# PUB3.net
KiCad netlist of a schematic drawn in EasyEDA Pro
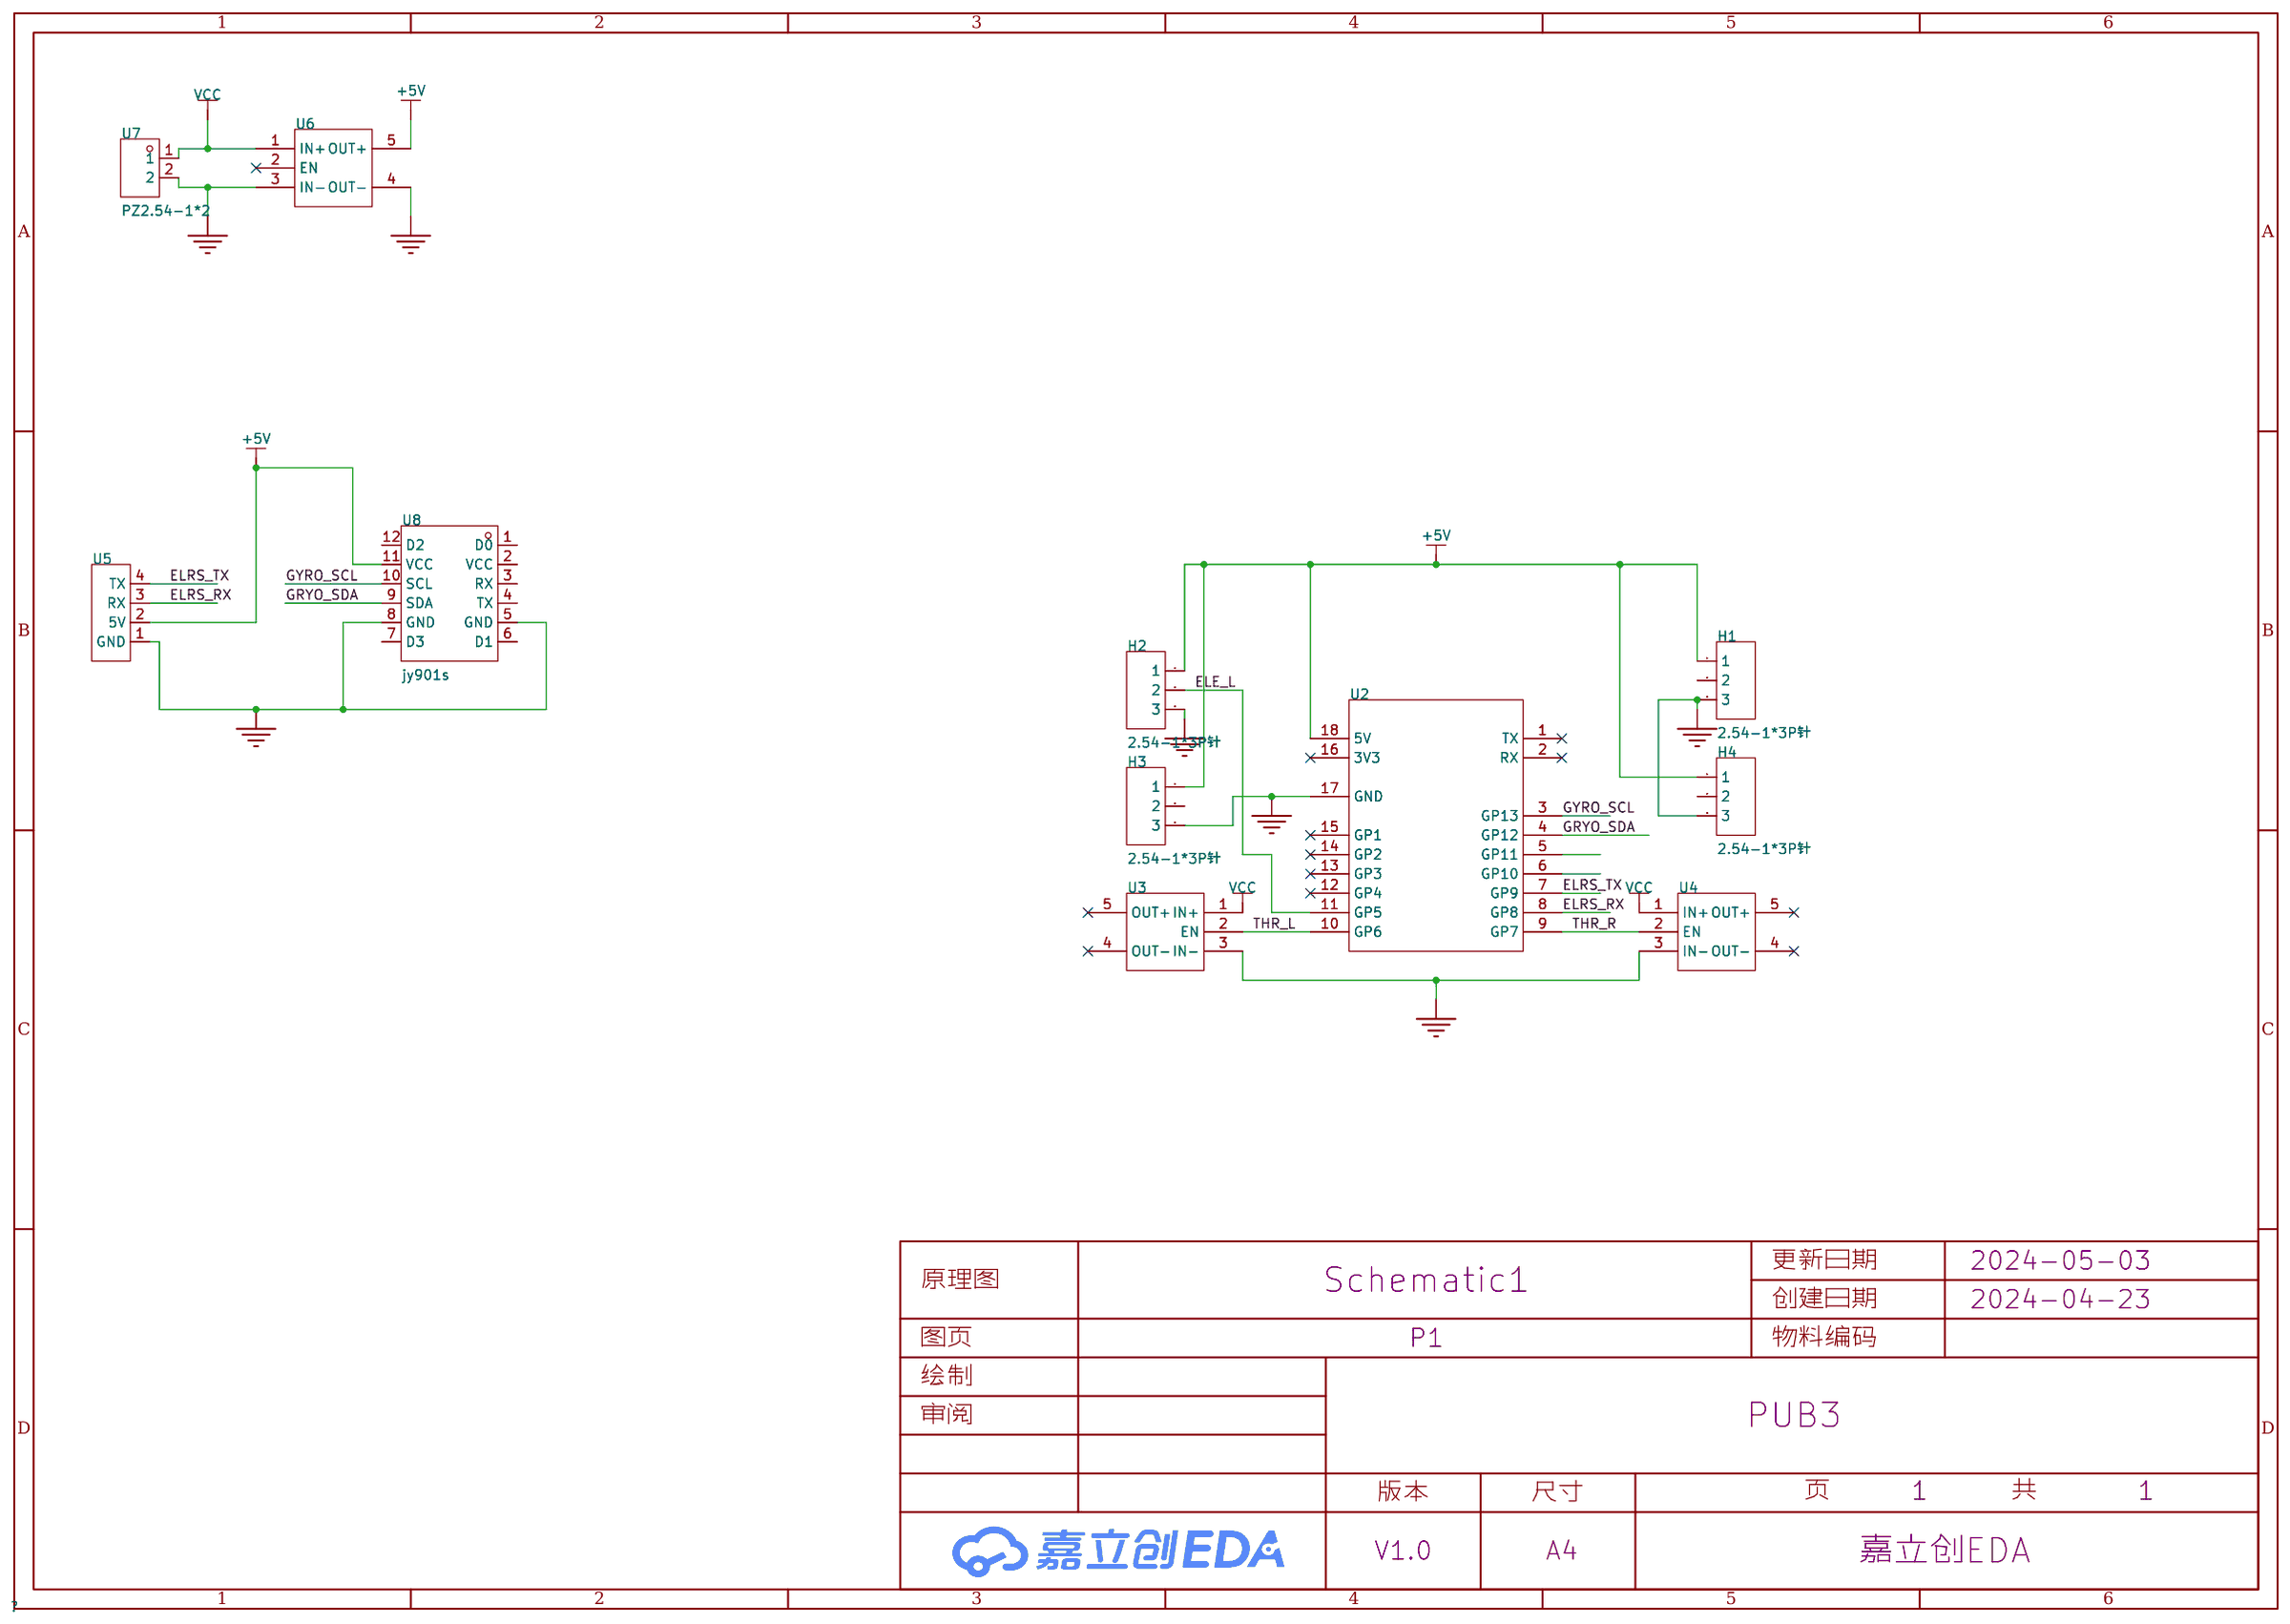
[diagram p0: schematic sheet]

(export (version "E")
  (design (tool "Eeschema 10.0.6"))
  (components
    (comp (ref "H1")
      (value "2.54-1*3P针")
      (footprint "easyedapro:HDR-TH_3P-P2.54-V-M-1")
      (fields (field (name "Manufacturer") "BOOMELE(博穆精密)"))
      (libsource (lib "easyedapro") (part "Header-Male-2.54_1x3"))
    )
    (comp (ref "H2")
      (value "2.54-1*3P针")
      (footprint "easyedapro:HDR-TH_3P-P2.54-V-M-1")
      (fields (field (name "Manufacturer") "BOOMELE(博穆精密)"))
      (libsource (lib "easyedapro") (part "Header-Male-2.54_1x3"))
    )
    (comp (ref "H3")
      (value "2.54-1*3P针")
      (footprint "easyedapro:HDR-TH_3P-P2.54-V-M-1")
      (fields (field (name "Manufacturer") "BOOMELE(博穆精密)"))
      (libsource (lib "easyedapro") (part "Header-Male-2.54_1x3"))
    )
    (comp (ref "H4")
      (value "2.54-1*3P针")
      (footprint "easyedapro:HDR-TH_3P-P2.54-V-M-1")
      (fields (field (name "Manufacturer") "BOOMELE(博穆精密)"))
      (libsource (lib "easyedapro") (part "Header-Male-2.54_1x3"))
    )
    (comp (ref "U2")
      (value "~")
      (footprint "easyedapro:ESP32-S3-Zero")
      (libsource (lib "easyedapro") (part "ESP32-S3-Zero"))
    )
    (comp (ref "U3")
      (value "~")
      (footprint "easyedapro:带有使能端的DC-DC降压模块")
      (libsource (lib "easyedapro") (part "带有使能端的DC-DC降压模块"))
    )
    (comp (ref "U4")
      (value "~")
      (footprint "easyedapro:带有使能端的DC-DC降压模块")
      (libsource (lib "easyedapro") (part "带有使能端的DC-DC降压模块"))
    )
    (comp (ref "U5")
      (value "~")
      (footprint "easyedapro:ELRS焊盘")
      (libsource (lib "easyedapro") (part "ELRS焊盘"))
    )
    (comp (ref "U6")
      (value "~")
      (footprint "easyedapro:带有使能端的DC-DC降压模块")
      (libsource (lib "easyedapro") (part "带有使能端的DC-DC降压模块"))
    )
    (comp (ref "U7")
      (value "PZ2.54-1*2")
      (footprint "easyedapro:HDR-TH_2P-P2.54-V-M-3")
      (fields (field (name "Manufacturer") "ZHOURI(洲日)"))
      (libsource (lib "easyedapro") (part "PZ2.54-1*2"))
    )
    (comp (ref "U8")
      (value "jy901s")
      (footprint "easyedapro:COMM-SMD_JY901S-1")
      (libsource (lib "easyedapro") (part "JY901S"))
    )
  )
  (nets
    (net (code "1") (name "+5V") (class "Default")
      (node (ref "H1") (pin "1") (pinfunction "1_1") (pintype "input"))
      (node (ref "H2") (pin "1") (pinfunction "1_1") (pintype "input"))
      (node (ref "H3") (pin "1") (pinfunction "1_1") (pintype "input"))
      (node (ref "H4") (pin "1") (pinfunction "1_1") (pintype "input"))
      (node (ref "U2") (pin "18") (pinfunction "5V_18") (pintype "input"))
      (node (ref "U5") (pin "2") (pinfunction "5V_2") (pintype "input"))
      (node (ref "U6") (pin "5") (pinfunction "OUT+_5") (pintype "output"))
      (node (ref "U8") (pin "11") (pinfunction "VCC_11") (pintype "unspecified"))
    )
    (net (code "2") (name "/ELE_L") (class "Default")
      (node (ref "H2") (pin "2") (pinfunction "2_2") (pintype "input"))
      (node (ref "U2") (pin "11") (pinfunction "GP5_11") (pintype "input"))
    )
    (net (code "3") (name "/ELRS_RX") (class "Default")
      (node (ref "U2") (pin "8") (pinfunction "GP8_8") (pintype "input"))
      (node (ref "U5") (pin "3") (pinfunction "RX_3") (pintype "input"))
    )
    (net (code "4") (name "/ELRS_TX") (class "Default")
      (node (ref "U2") (pin "7") (pinfunction "GP9_7") (pintype "input"))
      (node (ref "U5") (pin "4") (pinfunction "TX_4") (pintype "input"))
    )
    (net (code "5") (name "/GRYO_SDA") (class "Default")
      (node (ref "U2") (pin "4") (pinfunction "GP12_4") (pintype "input"))
      (node (ref "U8") (pin "9") (pinfunction "SDA_9") (pintype "unspecified"))
    )
    (net (code "6") (name "/GYRO_SCL") (class "Default")
      (node (ref "U2") (pin "3") (pinfunction "GP13_3") (pintype "input"))
      (node (ref "U8") (pin "10") (pinfunction "SCL_10") (pintype "unspecified"))
    )
    (net (code "7") (name "/THR_L") (class "Default")
      (node (ref "U2") (pin "10") (pinfunction "GP6_10") (pintype "input"))
      (node (ref "U3") (pin "2") (pinfunction "EN_2") (pintype "input"))
    )
    (net (code "8") (name "/THR_R") (class "Default")
      (node (ref "U2") (pin "9") (pinfunction "GP7_9") (pintype "input"))
      (node (ref "U4") (pin "2") (pinfunction "EN_2") (pintype "input"))
    )
    (net (code "9") (name "GND") (class "Default")
      (node (ref "H1") (pin "3") (pinfunction "3_3") (pintype "input"))
      (node (ref "H2") (pin "3") (pinfunction "3_3") (pintype "input"))
      (node (ref "H3") (pin "3") (pinfunction "3_3") (pintype "input"))
      (node (ref "H4") (pin "3") (pinfunction "3_3") (pintype "input"))
      (node (ref "U2") (pin "17") (pinfunction "GND_17") (pintype "input"))
      (node (ref "U3") (pin "3") (pinfunction "IN-_3") (pintype "input"))
      (node (ref "U4") (pin "3") (pinfunction "IN-_3") (pintype "input"))
      (node (ref "U5") (pin "1") (pinfunction "GND_1") (pintype "input"))
      (node (ref "U6") (pin "3") (pinfunction "IN-_3") (pintype "input"))
      (node (ref "U6") (pin "4") (pinfunction "OUT-_4") (pintype "output"))
      (node (ref "U7") (pin "2") (pinfunction "2_2") (pintype "unspecified"))
      (node (ref "U8") (pin "5") (pinfunction "GND_5") (pintype "unspecified"))
      (node (ref "U8") (pin "8") (pinfunction "GND_8") (pintype "unspecified"))
    )
    (net (code "10") (name "VCC") (class "Default")
      (node (ref "U3") (pin "1") (pinfunction "IN+_1") (pintype "input"))
      (node (ref "U4") (pin "1") (pinfunction "IN+_1") (pintype "input"))
      (node (ref "U6") (pin "1") (pinfunction "IN+_1") (pintype "input"))
      (node (ref "U7") (pin "1") (pinfunction "1_1") (pintype "unspecified"))
    )
    (net (code "11") (name "unconnected-(H1-Pad2)") (class "Default")
      (node (ref "H1") (pin "2") (pinfunction "2_2") (pintype "input"))
    )
    (net (code "12") (name "unconnected-(H3-Pad2)") (class "Default")
      (node (ref "H3") (pin "2") (pinfunction "2_2") (pintype "input"))
    )
    (net (code "13") (name "unconnected-(H4-Pad2)") (class "Default")
      (node (ref "H4") (pin "2") (pinfunction "2_2") (pintype "input"))
    )
    (net (code "14") (name "unconnected-(U2-3V3-Pad16)") (class "Default")
      (node (ref "U2") (pin "16") (pinfunction "3V3_16") (pintype "input+no_connect"))
    )
    (net (code "15") (name "unconnected-(U2-GP1-Pad15)") (class "Default")
      (node (ref "U2") (pin "15") (pinfunction "GP1_15") (pintype "input+no_connect"))
    )
    (net (code "16") (name "unconnected-(U2-GP2-Pad14)") (class "Default")
      (node (ref "U2") (pin "14") (pinfunction "GP2_14") (pintype "input+no_connect"))
    )
    (net (code "17") (name "unconnected-(U2-GP3-Pad13)") (class "Default")
      (node (ref "U2") (pin "13") (pinfunction "GP3_13") (pintype "input+no_connect"))
    )
    (net (code "18") (name "unconnected-(U2-GP4-Pad12)") (class "Default")
      (node (ref "U2") (pin "12") (pinfunction "GP4_12") (pintype "input+no_connect"))
    )
    (net (code "19") (name "unconnected-(U2-GP10-Pad6)") (class "Default")
      (node (ref "U2") (pin "6") (pinfunction "GP10_6") (pintype "input"))
    )
    (net (code "20") (name "unconnected-(U2-GP11-Pad5)") (class "Default")
      (node (ref "U2") (pin "5") (pinfunction "GP11_5") (pintype "input"))
    )
    (net (code "21") (name "unconnected-(U2-RX-Pad2)") (class "Default")
      (node (ref "U2") (pin "2") (pinfunction "RX_2") (pintype "input+no_connect"))
    )
    (net (code "22") (name "unconnected-(U2-TX-Pad1)") (class "Default")
      (node (ref "U2") (pin "1") (pinfunction "TX_1") (pintype "input+no_connect"))
    )
    (net (code "23") (name "unconnected-(U3-OUT+-Pad5)") (class "Default")
      (node (ref "U3") (pin "5") (pinfunction "OUT+_5") (pintype "output+no_connect"))
    )
    (net (code "24") (name "unconnected-(U3-OUT--Pad4)") (class "Default")
      (node (ref "U3") (pin "4") (pinfunction "OUT-_4") (pintype "output+no_connect"))
    )
    (net (code "25") (name "unconnected-(U4-OUT+-Pad5)") (class "Default")
      (node (ref "U4") (pin "5") (pinfunction "OUT+_5") (pintype "output+no_connect"))
    )
    (net (code "26") (name "unconnected-(U4-OUT--Pad4)") (class "Default")
      (node (ref "U4") (pin "4") (pinfunction "OUT-_4") (pintype "output+no_connect"))
    )
    (net (code "27") (name "unconnected-(U6-EN-Pad2)") (class "Default")
      (node (ref "U6") (pin "2") (pinfunction "EN_2") (pintype "input+no_connect"))
    )
    (net (code "28") (name "unconnected-(U8-D0-Pad1)") (class "Default")
      (node (ref "U8") (pin "1") (pinfunction "D0_1") (pintype "unspecified"))
    )
    (net (code "29") (name "unconnected-(U8-D1-Pad6)") (class "Default")
      (node (ref "U8") (pin "6") (pinfunction "D1_6") (pintype "unspecified"))
    )
    (net (code "30") (name "unconnected-(U8-D2-Pad12)") (class "Default")
      (node (ref "U8") (pin "12") (pinfunction "D2_12") (pintype "unspecified"))
    )
    (net (code "31") (name "unconnected-(U8-D3-Pad7)") (class "Default")
      (node (ref "U8") (pin "7") (pinfunction "D3_7") (pintype "unspecified"))
    )
    (net (code "32") (name "unconnected-(U8-RX-Pad3)") (class "Default")
      (node (ref "U8") (pin "3") (pinfunction "RX_3") (pintype "unspecified"))
    )
    (net (code "33") (name "unconnected-(U8-TX-Pad4)") (class "Default")
      (node (ref "U8") (pin "4") (pinfunction "TX_4") (pintype "unspecified"))
    )
    (net (code "34") (name "unconnected-(U8-VCC-Pad2)") (class "Default")
      (node (ref "U8") (pin "2") (pinfunction "VCC_2") (pintype "unspecified"))
    )
  )
)
